# 4-Mode_Regulator_Schematic.net
KiCad netlist of a schematic drawn in Altium Designer
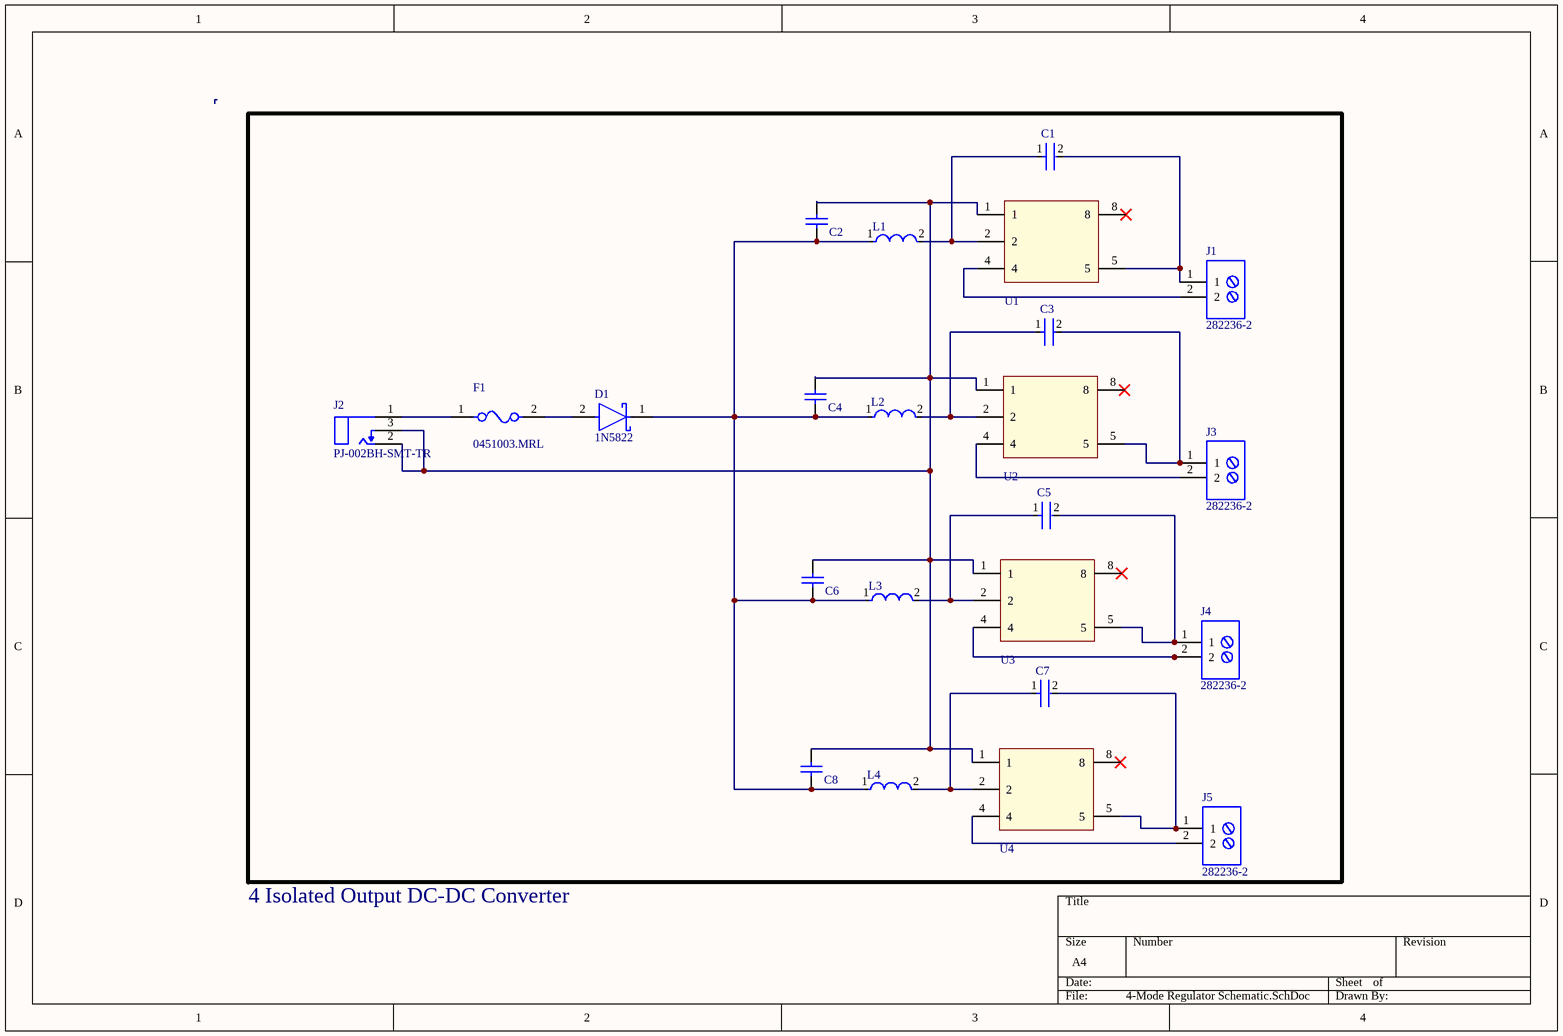
[diagram p0: 4-Mode Regulator Schematic.SchDoc]

(export (version "E")
  (design (tool "Eeschema 10.0.6"))
  (components
    (comp (ref "C1")
      (value "HV1812Y471KXMATHV")
      (footprint "FP-HV1812-IPC_C")
      (description "CAP CER 470PF 5KV X7R 1812")
      (fields (field (name "TOLERANCE") "10%"))
      (libsource (lib "Altium Content Vault") (part "11868f565c42a9108669ba33697ecf6"))
    )
    (comp (ref "C2")
      (value "GRM21BR71C225KA12L")
      (footprint "CAPC2013X135X50ML10T20")
      (fields (field (name "MANUFACTURER") "Murata"))
      (libsource (lib "Altium Content Vault") (part "CAP"))
    )
    (comp (ref "C3")
      (value "HV1812Y471KXMATHV")
      (footprint "FP-HV1812-IPC_C")
      (description "CAP CER 470PF 5KV X7R 1812")
      (fields (field (name "TOLERANCE") "10%"))
      (libsource (lib "Altium Content Vault") (part "11868f565c42a9108669ba33697ecf6"))
    )
    (comp (ref "C4")
      (value "GRM21BR71C225KA12L")
      (footprint "CAPC2013X135X50ML10T20")
      (fields (field (name "MANUFACTURER") "Murata"))
      (libsource (lib "Altium Content Vault") (part "CAP"))
    )
    (comp (ref "C5")
      (value "HV1812Y471KXMATHV")
      (footprint "FP-HV1812-IPC_C")
      (description "CAP CER 470PF 5KV X7R 1812")
      (fields (field (name "TOLERANCE") "10%"))
      (libsource (lib "Altium Content Vault") (part "11868f565c42a9108669ba33697ecf6"))
    )
    (comp (ref "C6")
      (value "GRM21BR71C225KA12L")
      (footprint "CAPC2013X135X50ML10T20")
      (fields (field (name "MANUFACTURER") "Murata"))
      (libsource (lib "Altium Content Vault") (part "CAP"))
    )
    (comp (ref "C7")
      (value "HV1812Y471KXMATHV")
      (footprint "FP-HV1812-IPC_C")
      (description "CAP CER 470PF 5KV X7R 1812")
      (fields (field (name "TOLERANCE") "10%"))
      (libsource (lib "Altium Content Vault") (part "11868f565c42a9108669ba33697ecf6"))
    )
    (comp (ref "C8")
      (value "GRM21BR71C225KA12L")
      (footprint "CAPC2013X135X50ML10T20")
      (fields (field (name "MANUFACTURER") "Murata"))
      (libsource (lib "Altium Content Vault") (part "CAP"))
    )
    (comp (ref "D1")
      (value "1N5822")
      (footprint "FP-B-Body-MFG")
      (description "1N5822 Diode Schottky 40V 3A 2-Pin Axial B-MELF Bag - Bulk")
      (libsource (lib "Altium Content Vault") (part "1d6ec82d83fb6aee721767c19dac4b9"))
    )
    (comp (ref "F1")
      (value "0451003.MRL")
      (footprint "FP-0451-MFG")
      (description "FUSE BRD MNT 3A 125VAC/VDC 2SMD")
      (fields
        (field (name "MANUFACTURER") "Littelfuse Inc")
        (field (name "OCTOPART") "https://octopart.com/0451003.mrl-littelfuse-566380")
      )
      (libsource (lib "Altium Content Vault") (part "5bcf9b9f640e542cf0359d10258e979"))
    )
    (comp (ref "J1")
      (value "282236-2")
      (footprint "282236-2")
      (description "Modular Terminal Block, 13.5A, 1.5mm2, 1 Row(s), 1 Deck(s)")
      (fields
        (field (name "MANUFACTURER") "TE Connectivity")
        (field (name "MANUFACTURER PART NUMBER") "282836-2")
        (field (name "SAFETY APPROVAL") "UL")
      )
      (libsource (lib "Lib") (part "282236-2"))
    )
    (comp (ref "J2")
      (value "PJ-002BH-SMT-TR")
      (footprint "FP-PJ-002BH-SMT-TR-MFG")
      (description "CONN PWR JACK 2.5X5.5MM SOLDER")
      (fields
        (field (name "MANUFACTURER") "CUI Inc")
        (field (name "OCTOPART") "https://octopart.com/pj-002bh-smt-tr-cui-25947151")
      )
      (libsource (lib "Altium Content Vault") (part "020ff674638626da6de6501228ee46e"))
    )
    (comp (ref "J3")
      (value "282236-2")
      (footprint "282236-2")
      (description "Modular Terminal Block, 13.5A, 1.5mm2, 1 Row(s), 1 Deck(s)")
      (fields
        (field (name "MANUFACTURER") "TE Connectivity")
        (field (name "MANUFACTURER PART NUMBER") "282836-2")
        (field (name "SAFETY APPROVAL") "UL")
      )
      (libsource (lib "Lib") (part "282236-2"))
    )
    (comp (ref "J4")
      (value "282236-2")
      (footprint "282236-2")
      (description "Modular Terminal Block, 13.5A, 1.5mm2, 1 Row(s), 1 Deck(s)")
      (fields
        (field (name "MANUFACTURER") "TE Connectivity")
        (field (name "MANUFACTURER PART NUMBER") "282836-2")
        (field (name "SAFETY APPROVAL") "UL")
      )
      (libsource (lib "Lib") (part "282236-2"))
    )
    (comp (ref "J5")
      (value "282236-2")
      (footprint "282236-2")
      (description "Modular Terminal Block, 13.5A, 1.5mm2, 1 Row(s), 1 Deck(s)")
      (fields
        (field (name "MANUFACTURER") "TE Connectivity")
        (field (name "MANUFACTURER PART NUMBER") "282836-2")
        (field (name "SAFETY APPROVAL") "UL")
      )
      (libsource (lib "Lib") (part "282236-2"))
    )
    (comp (ref "L1")
      (value "IHLP2020BZER100M01")
      (footprint "FP-IHLP-2020BZ-FP_1_905x2-MFG")
      (description "Fixed Inductors Commercial High Saturation Series 10uH 2.3A 199mΩ 20%")
      (fields (field (name "TOLERANCE") "20%"))
      (libsource (lib "Altium Content Vault") (part "725321dda6339637d4d059423bc1c3c"))
    )
    (comp (ref "L2")
      (value "IHLP2020BZER100M01")
      (footprint "FP-IHLP-2020BZ-FP_1_905x2-MFG")
      (description "Fixed Inductors Commercial High Saturation Series 10uH 2.3A 199mΩ 20%")
      (fields (field (name "TOLERANCE") "20%"))
      (libsource (lib "Altium Content Vault") (part "725321dda6339637d4d059423bc1c3c"))
    )
    (comp (ref "L3")
      (value "IHLP2020BZER100M01")
      (footprint "FP-IHLP-2020BZ-FP_1_905x2-MFG")
      (description "Fixed Inductors Commercial High Saturation Series 10uH 2.3A 199mΩ 20%")
      (fields (field (name "TOLERANCE") "20%"))
      (libsource (lib "Altium Content Vault") (part "725321dda6339637d4d059423bc1c3c"))
    )
    (comp (ref "L4")
      (value "IHLP2020BZER100M01")
      (footprint "FP-IHLP-2020BZ-FP_1_905x2-MFG")
      (description "Fixed Inductors Commercial High Saturation Series 10uH 2.3A 199mΩ 20%")
      (fields (field (name "TOLERANCE") "20%"))
      (libsource (lib "Altium Content Vault") (part "725321dda6339637d4d059423bc1c3c"))
    )
    (comp (ref "U1")
      (value "8-SMD Module, 5 Leads")
      (footprint "8-SMD Module, 5 Leads")
      (description "8-SMD Module, 5 Leads ICs")
      (fields (field (name "CREATED BY") "Arda Kara"))
      (libsource (lib "Lib") (part "8-SMD Module, 5 Leads"))
    )
    (comp (ref "U2")
      (value "8-SMD Module, 5 Leads")
      (footprint "8-SMD Module, 5 Leads")
      (description "8-SMD Module, 5 Leads ICs")
      (fields (field (name "CREATED BY") "Arda Kara"))
      (libsource (lib "Lib") (part "8-SMD Module, 5 Leads"))
    )
    (comp (ref "U3")
      (value "8-SMD Module, 5 Leads")
      (footprint "8-SMD Module, 5 Leads")
      (description "8-SMD Module, 5 Leads ICs")
      (fields (field (name "CREATED BY") "Arda Kara"))
      (libsource (lib "Lib") (part "8-SMD Module, 5 Leads"))
    )
    (comp (ref "U4")
      (value "8-SMD Module, 5 Leads")
      (footprint "8-SMD Module, 5 Leads")
      (description "8-SMD Module, 5 Leads ICs")
      (fields (field (name "CREATED BY") "Arda Kara"))
      (libsource (lib "Lib") (part "8-SMD Module, 5 Leads"))
    )
  )
  (nets
    (net (code "1") (name "Net-(C1-Pad1)") (class "Default")
      (node (ref "C1") (pin "1") (pinfunction "1_1") (pintype "passive"))
      (node (ref "L1") (pin "2") (pinfunction "2_2") (pintype "passive"))
      (node (ref "U1") (pin "2") (pinfunction "2_2") (pintype "passive"))
    )
    (net (code "2") (name "Net-(C1-Pad2)") (class "Default")
      (node (ref "C1") (pin "2") (pinfunction "2_2") (pintype "passive"))
      (node (ref "J1") (pin "1") (pinfunction "1_1") (pintype "passive"))
      (node (ref "U1") (pin "5") (pinfunction "5_5") (pintype "passive"))
    )
    (net (code "3") (name "Net-(C2-Pad2)") (class "Default")
      (node (ref "C2") (pin "2") (pinfunction "2_2") (pintype "passive"))
      (node (ref "C4") (pin "2") (pinfunction "2_2") (pintype "passive"))
      (node (ref "C6") (pin "2") (pinfunction "2_2") (pintype "passive"))
      (node (ref "C8") (pin "2") (pinfunction "2_2") (pintype "passive"))
      (node (ref "J2") (pin "2") (pinfunction "2_2") (pintype "passive"))
      (node (ref "J2") (pin "3") (pinfunction "3_3") (pintype "passive"))
      (node (ref "U1") (pin "1") (pinfunction "1_1") (pintype "passive"))
      (node (ref "U2") (pin "1") (pinfunction "1_1") (pintype "passive"))
      (node (ref "U3") (pin "1") (pinfunction "1_1") (pintype "passive"))
      (node (ref "U4") (pin "1") (pinfunction "1_1") (pintype "passive"))
    )
    (net (code "4") (name "Net-(C3-Pad1)") (class "Default")
      (node (ref "C3") (pin "1") (pinfunction "1_1") (pintype "passive"))
      (node (ref "L2") (pin "2") (pinfunction "2_2") (pintype "passive"))
      (node (ref "U2") (pin "2") (pinfunction "2_2") (pintype "passive"))
    )
    (net (code "5") (name "Net-(C3-Pad2)") (class "Default")
      (node (ref "C3") (pin "2") (pinfunction "2_2") (pintype "passive"))
      (node (ref "J3") (pin "1") (pinfunction "1_1") (pintype "passive"))
      (node (ref "U2") (pin "5") (pinfunction "5_5") (pintype "passive"))
    )
    (net (code "6") (name "Net-(C5-Pad1)") (class "Default")
      (node (ref "C5") (pin "1") (pinfunction "1_1") (pintype "passive"))
      (node (ref "L3") (pin "2") (pinfunction "2_2") (pintype "passive"))
      (node (ref "U3") (pin "2") (pinfunction "2_2") (pintype "passive"))
    )
    (net (code "7") (name "Net-(C5-Pad2)") (class "Default")
      (node (ref "C5") (pin "2") (pinfunction "2_2") (pintype "passive"))
      (node (ref "J4") (pin "1") (pinfunction "1_1") (pintype "passive"))
      (node (ref "U3") (pin "5") (pinfunction "5_5") (pintype "passive"))
    )
    (net (code "8") (name "Net-(C7-Pad1)") (class "Default")
      (node (ref "C7") (pin "1") (pinfunction "1_1") (pintype "passive"))
      (node (ref "L4") (pin "2") (pinfunction "2_2") (pintype "passive"))
      (node (ref "U4") (pin "2") (pinfunction "2_2") (pintype "passive"))
    )
    (net (code "9") (name "Net-(C7-Pad2)") (class "Default")
      (node (ref "C7") (pin "2") (pinfunction "2_2") (pintype "passive"))
      (node (ref "J5") (pin "1") (pinfunction "1_1") (pintype "passive"))
      (node (ref "U4") (pin "5") (pinfunction "5_5") (pintype "passive"))
    )
    (net (code "10") (name "Net-(D1-A)") (class "Default")
      (node (ref "D1") (pin "2") (pinfunction "A_2") (pintype "passive"))
      (node (ref "F1") (pin "2") (pinfunction "2_2") (pintype "passive"))
    )
    (net (code "11") (name "Net-(D1-C)") (class "Default")
      (node (ref "C2") (pin "1") (pinfunction "1_1") (pintype "passive"))
      (node (ref "C4") (pin "1") (pinfunction "1_1") (pintype "passive"))
      (node (ref "C6") (pin "1") (pinfunction "1_1") (pintype "passive"))
      (node (ref "C8") (pin "1") (pinfunction "1_1") (pintype "passive"))
      (node (ref "D1") (pin "1") (pinfunction "C_1") (pintype "passive"))
      (node (ref "L1") (pin "1") (pinfunction "1_1") (pintype "passive"))
      (node (ref "L2") (pin "1") (pinfunction "1_1") (pintype "passive"))
      (node (ref "L3") (pin "1") (pinfunction "1_1") (pintype "passive"))
      (node (ref "L4") (pin "1") (pinfunction "1_1") (pintype "passive"))
    )
    (net (code "12") (name "Net-(F1-Pad1)") (class "Default")
      (node (ref "F1") (pin "1") (pinfunction "1_1") (pintype "passive"))
      (node (ref "J2") (pin "1") (pinfunction "1_1") (pintype "passive"))
    )
    (net (code "13") (name "Net-(J1-Pad2)") (class "Default")
      (node (ref "J1") (pin "2") (pinfunction "2_2") (pintype "passive"))
      (node (ref "U1") (pin "4") (pinfunction "4_4") (pintype "passive"))
    )
    (net (code "14") (name "Net-(J3-Pad2)") (class "Default")
      (node (ref "J3") (pin "2") (pinfunction "2_2") (pintype "passive"))
      (node (ref "U2") (pin "4") (pinfunction "4_4") (pintype "passive"))
    )
    (net (code "15") (name "Net-(J4-Pad2)") (class "Default")
      (node (ref "J4") (pin "2") (pinfunction "2_2") (pintype "passive"))
      (node (ref "U3") (pin "4") (pinfunction "4_4") (pintype "passive"))
    )
    (net (code "16") (name "Net-(J5-Pad2)") (class "Default")
      (node (ref "J5") (pin "2") (pinfunction "2_2") (pintype "passive"))
      (node (ref "U4") (pin "4") (pinfunction "4_4") (pintype "passive"))
    )
    (net (code "17") (name "unconnected-(U1-Pad8)") (class "Default")
      (node (ref "U1") (pin "8") (pinfunction "8_8") (pintype "passive+no_connect"))
    )
    (net (code "18") (name "unconnected-(U2-Pad8)") (class "Default")
      (node (ref "U2") (pin "8") (pinfunction "8_8") (pintype "passive+no_connect"))
    )
    (net (code "19") (name "unconnected-(U3-Pad8)") (class "Default")
      (node (ref "U3") (pin "8") (pinfunction "8_8") (pintype "passive+no_connect"))
    )
    (net (code "20") (name "unconnected-(U4-Pad8)") (class "Default")
      (node (ref "U4") (pin "8") (pinfunction "8_8") (pintype "passive+no_connect"))
    )
  )
)
